# aepro_28C256.net
KiCad netlist of a schematic drawn in EAGLE
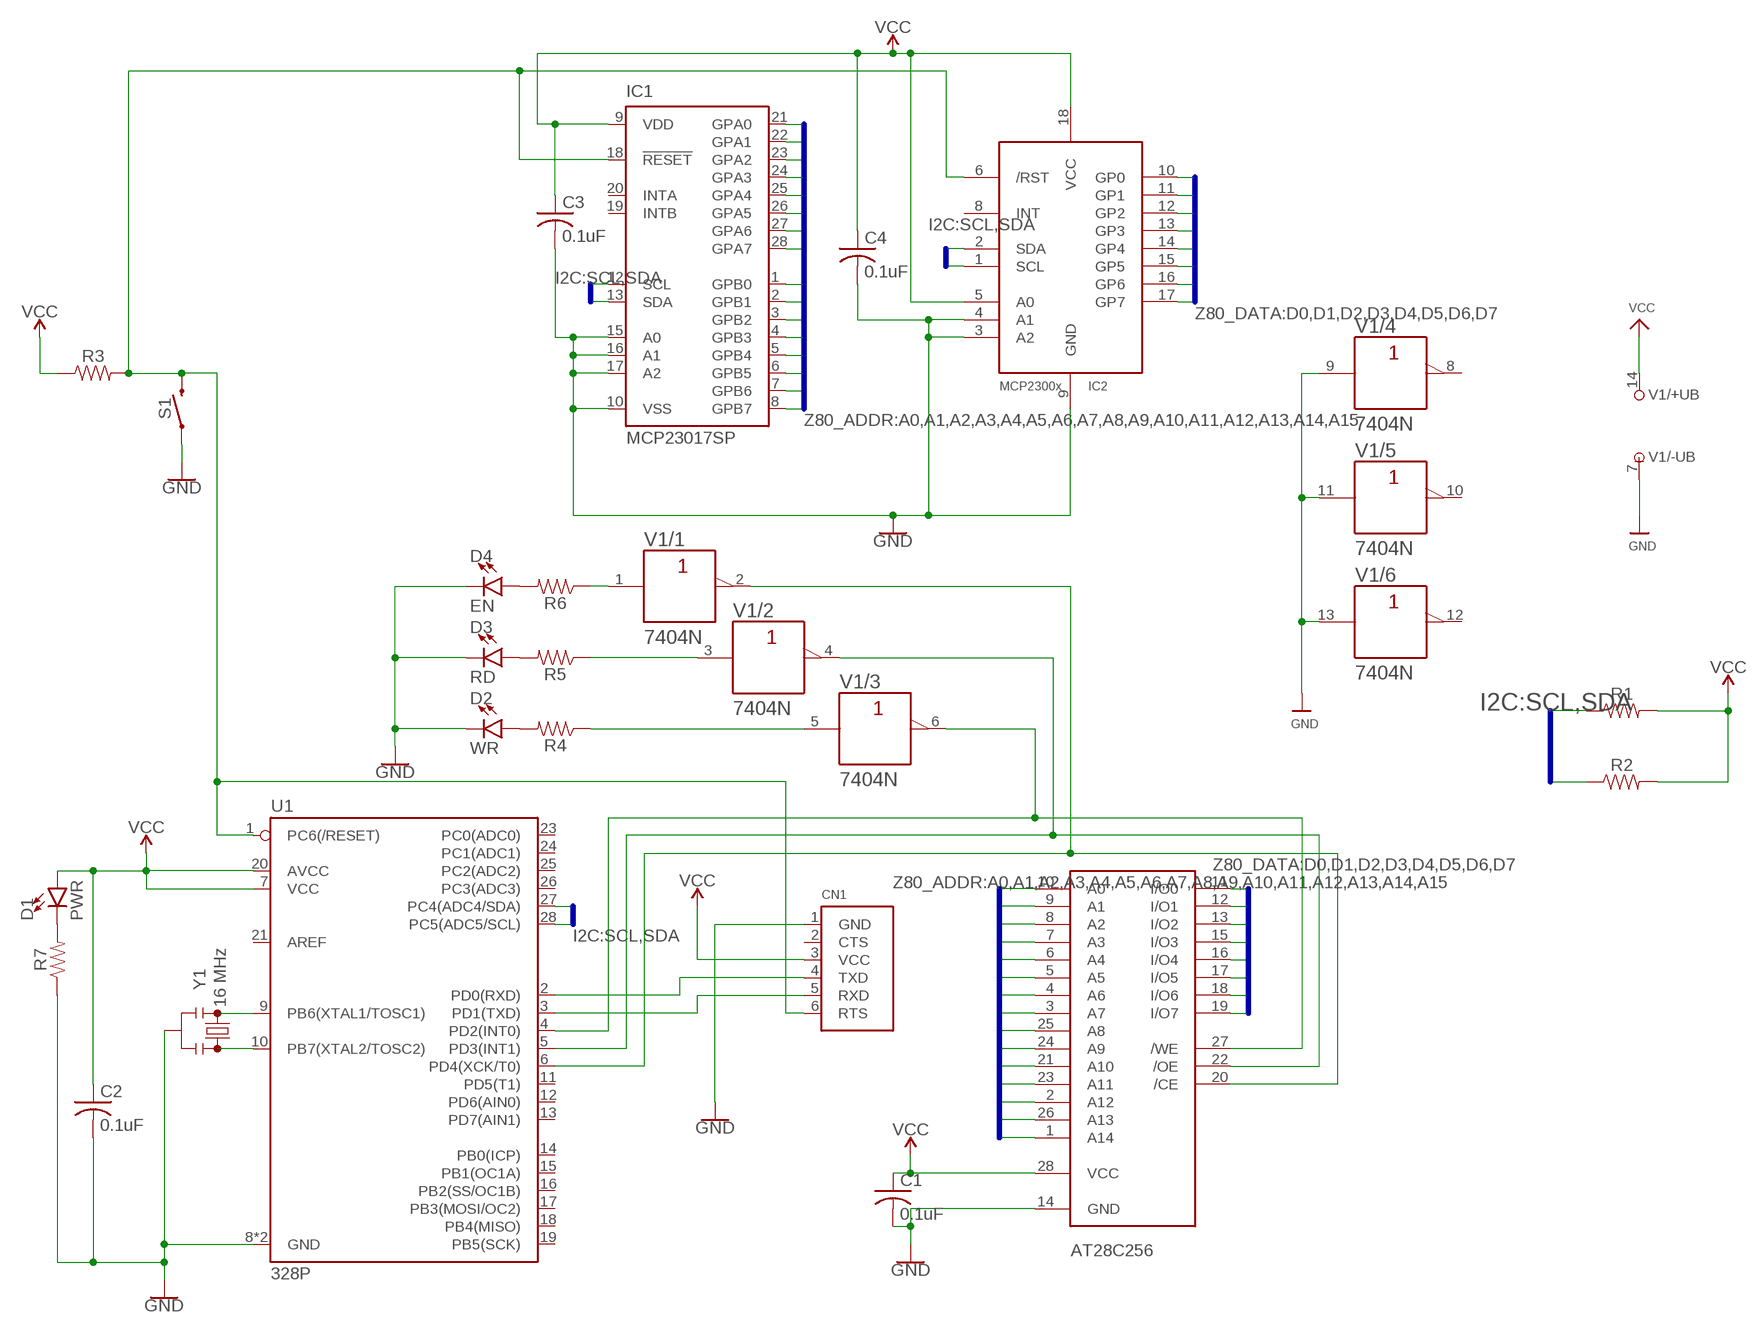
[diagram p0: schematic, sheet 1]

(export (version "E")
  (design (tool "Eeschema 10.0.6"))
  (components
    (comp (ref "C1")
      (value "0.1uF")
      (footprint "eagle-import:C050-024X044")
      (libsource (lib "eagle-import") (part "C-US050-024X044"))
    )
    (comp (ref "C2")
      (value "0.1uF")
      (footprint "eagle-import:C050-024X044")
      (libsource (lib "eagle-import") (part "C-US050-024X044"))
    )
    (comp (ref "C3")
      (value "0.1uF")
      (footprint "eagle-import:C050-024X044")
      (libsource (lib "eagle-import") (part "C-US050-024X044"))
    )
    (comp (ref "C4")
      (value "0.1uF")
      (footprint "eagle-import:C050-024X044")
      (libsource (lib "eagle-import") (part "C-US050-024X044"))
    )
    (comp (ref "CN1")
      (value "FTDIUSBCABLE")
      (footprint "eagle-import:1X06_ROUND")
      (libsource (lib "eagle-import") (part "FTDIUSBCABLE"))
    )
    (comp (ref "D1")
      (value "PWR")
      (footprint "eagle-import:LED_3MM")
      (libsource (lib "eagle-import") (part "LED3MM"))
    )
    (comp (ref "D2")
      (value "WR")
      (footprint "eagle-import:LED_3MM")
      (libsource (lib "eagle-import") (part "LED3MM"))
    )
    (comp (ref "D3")
      (value "RD")
      (footprint "eagle-import:LED_3MM")
      (libsource (lib "eagle-import") (part "LED3MM"))
    )
    (comp (ref "D4")
      (value "EN")
      (footprint "eagle-import:LED_3MM")
      (libsource (lib "eagle-import") (part "LED3MM"))
    )
    (comp (ref "IC1")
      (value "MCP23017SP")
      (footprint "eagle-import:DIL28-3")
      (libsource (lib "eagle-import") (part "MCP23017SP"))
    )
    (comp (ref "IC2")
      (value "MCP23008/P")
      (footprint "eagle-import:DIL18")
      (libsource (lib "eagle-import") (part "MCP23008/P"))
    )
    (comp (ref "R1")
      (value "RESISTORAXIAL-0.3")
      (footprint "eagle-import:AXIAL-0.3")
      (libsource (lib "eagle-import") (part "RESISTORAXIAL-0.3"))
    )
    (comp (ref "R2")
      (value "RESISTORAXIAL-0.3")
      (footprint "eagle-import:AXIAL-0.3")
      (libsource (lib "eagle-import") (part "RESISTORAXIAL-0.3"))
    )
    (comp (ref "R3")
      (value "RESISTORAXIAL-0.3")
      (footprint "eagle-import:AXIAL-0.3")
      (libsource (lib "eagle-import") (part "RESISTORAXIAL-0.3"))
    )
    (comp (ref "R4")
      (value "RESISTORAXIAL-0.3")
      (footprint "eagle-import:AXIAL-0.3")
      (libsource (lib "eagle-import") (part "RESISTORAXIAL-0.3"))
    )
    (comp (ref "R5")
      (value "RESISTORAXIAL-0.3")
      (footprint "eagle-import:AXIAL-0.3")
      (libsource (lib "eagle-import") (part "RESISTORAXIAL-0.3"))
    )
    (comp (ref "R6")
      (value "RESISTORAXIAL-0.3")
      (footprint "eagle-import:AXIAL-0.3")
      (libsource (lib "eagle-import") (part "RESISTORAXIAL-0.3"))
    )
    (comp (ref "R7")
      (value "RESISTORAXIAL-0.3")
      (footprint "eagle-import:AXIAL-0.3")
      (libsource (lib "eagle-import") (part "RESISTORAXIAL-0.3"))
    )
    (comp (ref "S1")
      (value "MOMENTARY-SWITCH-SPST-PTH-6.0MM")
      (footprint "eagle-import:TACTILE_SWITCH_PTH_6.0MM")
      (libsource (lib "eagle-import") (part "MOMENTARY-SWITCH-SPST-PTH-6.0MM"))
    )
    (comp (ref "U$1")
      (value "AT28C256")
      (footprint "eagle-import:DIL28-6-ZIF_SOCKET")
      (libsource (lib "eagle-import") (part "AT28C256"))
    )
    (comp (ref "U1")
      (value "328P")
      (footprint "eagle-import:DIP28")
      (libsource (lib "eagle-import") (part "ATMEGA328P_PDIP"))
    )
    (comp (ref "V1")
      (value "7404N")
      (footprint "eagle-import:DIL14")
      (libsource (lib "eagle-import") (part "7404N"))
    )
    (comp (ref "Y1")
      (value "16 MHz")
      (footprint "eagle-import:RESONATOR-PTH-7.6X3.8")
      (libsource (lib "eagle-import") (part "RESONATORPTH-7.6X3.8"))
    )
  )
  (nets
    (net (code "5") (name "/A1") (class "Default")
      (node (ref "IC1") (pin "22") (pinfunction "GPA1_22") (pintype "bidirectional"))
      (node (ref "U$1") (pin "9") (pinfunction "A1_9") (pintype "bidirectional"))
    )
    (net (code "6") (name "/A2") (class "Default")
      (node (ref "IC1") (pin "23") (pinfunction "GPA2_23") (pintype "bidirectional"))
      (node (ref "U$1") (pin "8") (pinfunction "A2_8") (pintype "bidirectional"))
    )
    (net (code "7") (name "/A3") (class "Default")
      (node (ref "IC1") (pin "24") (pinfunction "GPA3_24") (pintype "bidirectional"))
      (node (ref "U$1") (pin "7") (pinfunction "A3_7") (pintype "bidirectional"))
    )
    (net (code "8") (name "/A4") (class "Default")
      (node (ref "IC1") (pin "25") (pinfunction "GPA4_25") (pintype "bidirectional"))
      (node (ref "U$1") (pin "6") (pinfunction "A4_6") (pintype "bidirectional"))
    )
    (net (code "9") (name "/A5") (class "Default")
      (node (ref "IC1") (pin "26") (pinfunction "GPA5_26") (pintype "bidirectional"))
      (node (ref "U$1") (pin "5") (pinfunction "A5_5") (pintype "bidirectional"))
    )
    (net (code "10") (name "/A6") (class "Default")
      (node (ref "IC1") (pin "27") (pinfunction "GPA6_27") (pintype "bidirectional"))
      (node (ref "U$1") (pin "4") (pinfunction "A6_4") (pintype "bidirectional"))
    )
    (net (code "11") (name "/A7") (class "Default")
      (node (ref "IC1") (pin "28") (pinfunction "GPA7_28") (pintype "bidirectional"))
      (node (ref "U$1") (pin "3") (pinfunction "A7_3") (pintype "bidirectional"))
    )
    (net (code "12") (name "/A8") (class "Default")
      (node (ref "IC1") (pin "1") (pinfunction "GPB0_1") (pintype "bidirectional"))
      (node (ref "U$1") (pin "25") (pinfunction "A8_25") (pintype "bidirectional"))
    )
    (net (code "13") (name "/A9") (class "Default")
      (node (ref "IC1") (pin "2") (pinfunction "GPB1_2") (pintype "bidirectional"))
      (node (ref "U$1") (pin "24") (pinfunction "A9_24") (pintype "bidirectional"))
    )
    (net (code "14") (name "/A10") (class "Default")
      (node (ref "IC1") (pin "3") (pinfunction "GPB2_3") (pintype "bidirectional"))
      (node (ref "U$1") (pin "21") (pinfunction "A10_21") (pintype "bidirectional"))
    )
    (net (code "15") (name "/A11") (class "Default")
      (node (ref "IC1") (pin "4") (pinfunction "GPB3_4") (pintype "bidirectional"))
      (node (ref "U$1") (pin "23") (pinfunction "A11_23") (pintype "bidirectional"))
    )
    (net (code "16") (name "/A12") (class "Default")
      (node (ref "IC1") (pin "5") (pinfunction "GPB4_5") (pintype "bidirectional"))
      (node (ref "U$1") (pin "2") (pinfunction "A12_2") (pintype "bidirectional"))
    )
    (net (code "17") (name "/A13") (class "Default")
      (node (ref "IC1") (pin "6") (pinfunction "GPB5_6") (pintype "bidirectional"))
      (node (ref "U$1") (pin "26") (pinfunction "A13_26") (pintype "bidirectional"))
    )
    (net (code "18") (name "/A14") (class "Default")
      (node (ref "IC1") (pin "7") (pinfunction "GPB6_7") (pintype "bidirectional"))
      (node (ref "U$1") (pin "1") (pinfunction "A14_1") (pintype "bidirectional"))
    )
    (net (code "19") (name "/D1") (class "Default")
      (node (ref "IC2") (pin "11") (pinfunction "GP1_11") (pintype "bidirectional"))
      (node (ref "U$1") (pin "12") (pinfunction "I/O1_12") (pintype "bidirectional"))
    )
    (net (code "20") (name "/D2") (class "Default")
      (node (ref "IC2") (pin "12") (pinfunction "GP2_12") (pintype "bidirectional"))
      (node (ref "U$1") (pin "13") (pinfunction "I/O2_13") (pintype "bidirectional"))
    )
    (net (code "21") (name "/D3") (class "Default")
      (node (ref "IC2") (pin "13") (pinfunction "GP3_13") (pintype "bidirectional"))
      (node (ref "U$1") (pin "15") (pinfunction "I/O3_15") (pintype "bidirectional"))
    )
    (net (code "22") (name "/D4") (class "Default")
      (node (ref "IC2") (pin "14") (pinfunction "GP4_14") (pintype "bidirectional"))
      (node (ref "U$1") (pin "16") (pinfunction "I/O4_16") (pintype "bidirectional"))
    )
    (net (code "23") (name "/D5") (class "Default")
      (node (ref "IC2") (pin "15") (pinfunction "GP5_15") (pintype "bidirectional"))
      (node (ref "U$1") (pin "17") (pinfunction "I/O5_17") (pintype "bidirectional"))
    )
    (net (code "24") (name "/D6") (class "Default")
      (node (ref "IC2") (pin "16") (pinfunction "GP6_16") (pintype "bidirectional"))
      (node (ref "U$1") (pin "18") (pinfunction "I/O6_18") (pintype "bidirectional"))
    )
    (net (code "25") (name "/D7") (class "Default")
      (node (ref "IC2") (pin "17") (pinfunction "GP7_17") (pintype "bidirectional"))
      (node (ref "U$1") (pin "19") (pinfunction "I/O7_19") (pintype "bidirectional"))
    )
    (net (code "26") (name "/I2C:SCL") (class "Default")
      (node (ref "IC1") (pin "12") (pinfunction "SCL_12") (pintype "input"))
      (node (ref "IC2") (pin "1") (pinfunction "SCL_1") (pintype "bidirectional"))
      (node (ref "R1") (pin "P$1") (pinfunction "1_P$1") (pintype "passive"))
      (node (ref "U1") (pin "28") (pinfunction "PC5(ADC5/SCL)_28") (pintype "bidirectional"))
    )
    (net (code "27") (name "/SDA") (class "Default")
      (node (ref "IC1") (pin "13") (pinfunction "SDA_13") (pintype "bidirectional"))
      (node (ref "IC2") (pin "2") (pinfunction "SDA_2") (pintype "bidirectional"))
      (node (ref "R2") (pin "P$1") (pinfunction "1_P$1") (pintype "passive"))
      (node (ref "U1") (pin "27") (pinfunction "PC4(ADC4/SDA)_27") (pintype "bidirectional"))
    )
    (net (code "28") (name "/Z80_ADDR:A0") (class "Default")
      (node (ref "IC1") (pin "21") (pinfunction "GPA0_21") (pintype "bidirectional"))
      (node (ref "U$1") (pin "10") (pinfunction "A0_10") (pintype "bidirectional"))
    )
    (net (code "29") (name "/Z80_DATA:D0") (class "Default")
      (node (ref "IC2") (pin "10") (pinfunction "GP0_10") (pintype "bidirectional"))
      (node (ref "U$1") (pin "11") (pinfunction "I/O0_11") (pintype "bidirectional"))
    )
    (net (code "33") (name "GND") (class "Default")
      (node (ref "C1") (pin "2") (pinfunction "2_2") (pintype "passive"))
      (node (ref "C2") (pin "2") (pinfunction "2_2") (pintype "passive"))
      (node (ref "C3") (pin "2") (pinfunction "2_2") (pintype "passive"))
      (node (ref "C4") (pin "2") (pinfunction "2_2") (pintype "passive"))
      (node (ref "CN1") (pin "1") (pinfunction "GND_1") (pintype "bidirectional"))
      (node (ref "D2") (pin "K") (pinfunction "C_K") (pintype "passive"))
      (node (ref "D3") (pin "K") (pinfunction "C_K") (pintype "passive"))
      (node (ref "D4") (pin "K") (pinfunction "C_K") (pintype "passive"))
      (node (ref "IC1") (pin "10") (pinfunction "VSS_10") (pintype "power_in"))
      (node (ref "IC1") (pin "15") (pinfunction "A0_15") (pintype "input"))
      (node (ref "IC1") (pin "16") (pinfunction "A1_16") (pintype "input"))
      (node (ref "IC1") (pin "17") (pinfunction "A2_17") (pintype "input"))
      (node (ref "IC2") (pin "3") (pinfunction "A2_3") (pintype "input"))
      (node (ref "IC2") (pin "4") (pinfunction "A1_4") (pintype "input"))
      (node (ref "IC2") (pin "9") (pinfunction "GND_9") (pintype "power_in"))
      (node (ref "R7") (pin "P$1") (pinfunction "1_P$1") (pintype "passive"))
      (node (ref "S1") (pin "1") (pinfunction "1_1") (pintype "passive"))
      (node (ref "U$1") (pin "14") (pinfunction "GND_14") (pintype "bidirectional"))
      (node (ref "U1") (pin "22") (pinfunction "GND_22") (pintype "bidirectional"))
      (node (ref "U1") (pin "8") (pinfunction "GND_8") (pintype "bidirectional"))
      (node (ref "V1") (pin "11") (pinfunction "A_11") (pintype "input"))
      (node (ref "V1") (pin "13") (pinfunction "A_13") (pintype "input"))
      (node (ref "V1") (pin "7") (pinfunction "-UB_7") (pintype "power_in"))
      (node (ref "V1") (pin "9") (pinfunction "A_9") (pintype "input"))
      (node (ref "Y1") (pin "2") (pinfunction "2_2") (pintype "passive"))
    )
    (net (code "34") (name "Net-(CN1-RTS)") (class "Default")
      (node (ref "CN1") (pin "6") (pinfunction "RTS_6") (pintype "bidirectional"))
      (node (ref "IC1") (pin "18") (pinfunction "~{RESET}_18") (pintype "input"))
      (node (ref "IC2") (pin "6") (pinfunction "/RST_6") (pintype "input"))
      (node (ref "R3") (pin "P$2") (pinfunction "2_P$2") (pintype "passive"))
      (node (ref "S1") (pin "3") (pinfunction "2_3") (pintype "passive"))
      (node (ref "U1") (pin "1") (pinfunction "PC6(/RESET)_1") (pintype "bidirectional"))
    )
    (net (code "35") (name "Net-(CN1-RXD)") (class "Default")
      (node (ref "CN1") (pin "5") (pinfunction "RXD_5") (pintype "bidirectional"))
      (node (ref "U1") (pin "3") (pinfunction "PD1(TXD)_3") (pintype "bidirectional"))
    )
    (net (code "36") (name "Net-(CN1-TXD)") (class "Default")
      (node (ref "CN1") (pin "4") (pinfunction "TXD_4") (pintype "bidirectional"))
      (node (ref "U1") (pin "2") (pinfunction "PD0(RXD)_2") (pintype "bidirectional"))
    )
    (net (code "37") (name "Net-(D1-C)") (class "Default")
      (node (ref "D1") (pin "K") (pinfunction "C_K") (pintype "passive"))
      (node (ref "R7") (pin "P$2") (pinfunction "2_P$2") (pintype "passive"))
    )
    (net (code "38") (name "Net-(R4-1)") (class "Default")
      (node (ref "R4") (pin "P$1") (pinfunction "1_P$1") (pintype "passive"))
      (node (ref "V1") (pin "5") (pinfunction "A_5") (pintype "input"))
    )
    (net (code "39") (name "Net-(R4-2)") (class "Default")
      (node (ref "D2") (pin "A") (pinfunction "A_A") (pintype "passive"))
      (node (ref "R4") (pin "P$2") (pinfunction "2_P$2") (pintype "passive"))
    )
    (net (code "40") (name "Net-(R5-1)") (class "Default")
      (node (ref "R5") (pin "P$1") (pinfunction "1_P$1") (pintype "passive"))
      (node (ref "V1") (pin "3") (pinfunction "A_3") (pintype "input"))
    )
    (net (code "41") (name "Net-(R5-2)") (class "Default")
      (node (ref "D3") (pin "A") (pinfunction "A_A") (pintype "passive"))
      (node (ref "R5") (pin "P$2") (pinfunction "2_P$2") (pintype "passive"))
    )
    (net (code "42") (name "Net-(R6-1)") (class "Default")
      (node (ref "R6") (pin "P$1") (pinfunction "1_P$1") (pintype "passive"))
      (node (ref "V1") (pin "1") (pinfunction "A_1") (pintype "input"))
    )
    (net (code "43") (name "Net-(R6-2)") (class "Default")
      (node (ref "D4") (pin "A") (pinfunction "A_A") (pintype "passive"))
      (node (ref "R6") (pin "P$2") (pinfunction "2_P$2") (pintype "passive"))
    )
    (net (code "44") (name "Net-(U$1-{slash}CE)") (class "Default")
      (node (ref "U$1") (pin "20") (pinfunction "/CE_20") (pintype "bidirectional"))
      (node (ref "U1") (pin "6") (pinfunction "PD4(XCK/T0)_6") (pintype "bidirectional"))
      (node (ref "V1") (pin "2") (pinfunction "Y_2") (pintype "output"))
    )
    (net (code "45") (name "Net-(U$1-{slash}OE)") (class "Default")
      (node (ref "U$1") (pin "22") (pinfunction "/OE_22") (pintype "bidirectional"))
      (node (ref "U1") (pin "5") (pinfunction "PD3(INT1)_5") (pintype "bidirectional"))
      (node (ref "V1") (pin "4") (pinfunction "Y_4") (pintype "output"))
    )
    (net (code "46") (name "Net-(U$1-{slash}WE)") (class "Default")
      (node (ref "U$1") (pin "27") (pinfunction "/WE_27") (pintype "bidirectional"))
      (node (ref "U1") (pin "4") (pinfunction "PD2(INT0)_4") (pintype "bidirectional"))
      (node (ref "V1") (pin "6") (pinfunction "Y_6") (pintype "output"))
    )
    (net (code "47") (name "Net-(U1-PB6(XTAL1{slash}TOSC1))") (class "Default")
      (node (ref "U1") (pin "9") (pinfunction "PB6(XTAL1/TOSC1)_9") (pintype "bidirectional"))
      (node (ref "Y1") (pin "1") (pinfunction "1_1") (pintype "passive"))
    )
    (net (code "48") (name "Net-(U1-PB7(XTAL2{slash}TOSC2))") (class "Default")
      (node (ref "U1") (pin "10") (pinfunction "PB7(XTAL2/TOSC2)_10") (pintype "bidirectional"))
      (node (ref "Y1") (pin "3") (pinfunction "3_3") (pintype "passive"))
    )
    (net (code "49") (name "VCC") (class "Default")
      (node (ref "C1") (pin "1") (pinfunction "1_1") (pintype "passive"))
      (node (ref "C2") (pin "1") (pinfunction "1_1") (pintype "passive"))
      (node (ref "C3") (pin "1") (pinfunction "1_1") (pintype "passive"))
      (node (ref "C4") (pin "1") (pinfunction "1_1") (pintype "passive"))
      (node (ref "CN1") (pin "3") (pinfunction "VCC_3") (pintype "bidirectional"))
      (node (ref "D1") (pin "A") (pinfunction "A_A") (pintype "passive"))
      (node (ref "IC1") (pin "9") (pinfunction "VDD_9") (pintype "power_in"))
      (node (ref "IC2") (pin "18") (pinfunction "VCC_18") (pintype "power_in"))
      (node (ref "IC2") (pin "5") (pinfunction "A0_5") (pintype "input"))
      (node (ref "R1") (pin "P$2") (pinfunction "2_P$2") (pintype "passive"))
      (node (ref "R2") (pin "P$2") (pinfunction "2_P$2") (pintype "passive"))
      (node (ref "R3") (pin "P$1") (pinfunction "1_P$1") (pintype "passive"))
      (node (ref "U$1") (pin "28") (pinfunction "VCC_28") (pintype "bidirectional"))
      (node (ref "U1") (pin "20") (pinfunction "AVCC_20") (pintype "bidirectional"))
      (node (ref "U1") (pin "7") (pinfunction "VCC_7") (pintype "bidirectional"))
      (node (ref "V1") (pin "14") (pinfunction "+UB_14") (pintype "power_in"))
    )
    (net (code "50") (name "unconnected-(CN1-CTS-Pad2)") (class "Default")
      (node (ref "CN1") (pin "2") (pinfunction "CTS_2") (pintype "bidirectional"))
    )
    (net (code "51") (name "unconnected-(IC1-GPB7-Pad8)") (class "Default")
      (node (ref "IC1") (pin "8") (pinfunction "GPB7_8") (pintype "bidirectional"))
    )
    (net (code "52") (name "unconnected-(IC1-INTA-Pad20)") (class "Default")
      (node (ref "IC1") (pin "20") (pinfunction "INTA_20") (pintype "output"))
    )
    (net (code "53") (name "unconnected-(IC1-INTB-Pad19)") (class "Default")
      (node (ref "IC1") (pin "19") (pinfunction "INTB_19") (pintype "output"))
    )
    (net (code "54") (name "unconnected-(IC2-INT-Pad8)") (class "Default")
      (node (ref "IC2") (pin "8") (pinfunction "INT_8") (pintype "output"))
    )
    (net (code "55") (name "unconnected-(U1-AREF-Pad21)") (class "Default")
      (node (ref "U1") (pin "21") (pinfunction "AREF_21") (pintype "bidirectional"))
    )
    (net (code "56") (name "unconnected-(U1-PB0(ICP)-Pad14)") (class "Default")
      (node (ref "U1") (pin "14") (pinfunction "PB0(ICP)_14") (pintype "bidirectional"))
    )
    (net (code "57") (name "unconnected-(U1-PB1(OC1A)-Pad15)") (class "Default")
      (node (ref "U1") (pin "15") (pinfunction "PB1(OC1A)_15") (pintype "bidirectional"))
    )
    (net (code "58") (name "unconnected-(U1-PB2(SS{slash}OC1B)-Pad16)") (class "Default")
      (node (ref "U1") (pin "16") (pinfunction "PB2(SS/OC1B)_16") (pintype "bidirectional"))
    )
    (net (code "59") (name "unconnected-(U1-PB3(MOSI{slash}OC2)-Pad17)") (class "Default")
      (node (ref "U1") (pin "17") (pinfunction "PB3(MOSI/OC2)_17") (pintype "bidirectional"))
    )
    (net (code "60") (name "unconnected-(U1-PB4(MISO)-Pad18)") (class "Default")
      (node (ref "U1") (pin "18") (pinfunction "PB4(MISO)_18") (pintype "bidirectional"))
    )
    (net (code "61") (name "unconnected-(U1-PB5(SCK)-Pad19)") (class "Default")
      (node (ref "U1") (pin "19") (pinfunction "PB5(SCK)_19") (pintype "bidirectional"))
    )
    (net (code "62") (name "unconnected-(U1-PC0(ADC0)-Pad23)") (class "Default")
      (node (ref "U1") (pin "23") (pinfunction "PC0(ADC0)_23") (pintype "bidirectional"))
    )
    (net (code "63") (name "unconnected-(U1-PC1(ADC1)-Pad24)") (class "Default")
      (node (ref "U1") (pin "24") (pinfunction "PC1(ADC1)_24") (pintype "bidirectional"))
    )
    (net (code "64") (name "unconnected-(U1-PC2(ADC2)-Pad25)") (class "Default")
      (node (ref "U1") (pin "25") (pinfunction "PC2(ADC2)_25") (pintype "bidirectional"))
    )
    (net (code "65") (name "unconnected-(U1-PC3(ADC3)-Pad26)") (class "Default")
      (node (ref "U1") (pin "26") (pinfunction "PC3(ADC3)_26") (pintype "bidirectional"))
    )
    (net (code "66") (name "unconnected-(U1-PD5(T1)-Pad11)") (class "Default")
      (node (ref "U1") (pin "11") (pinfunction "PD5(T1)_11") (pintype "bidirectional"))
    )
    (net (code "67") (name "unconnected-(U1-PD6(AIN0)-Pad12)") (class "Default")
      (node (ref "U1") (pin "12") (pinfunction "PD6(AIN0)_12") (pintype "bidirectional"))
    )
    (net (code "68") (name "unconnected-(U1-PD7(AIN1)-Pad13)") (class "Default")
      (node (ref "U1") (pin "13") (pinfunction "PD7(AIN1)_13") (pintype "bidirectional"))
    )
    (net (code "69") (name "unconnected-(V1F-Y-Pad8)") (class "Default")
      (node (ref "V1") (pin "8") (pinfunction "Y_8") (pintype "output"))
    )
    (net (code "70") (name "unconnected-(V1G-Y-Pad10)") (class "Default")
      (node (ref "V1") (pin "10") (pinfunction "Y_10") (pintype "output"))
    )
    (net (code "71") (name "unconnected-(V1H-Y-Pad12)") (class "Default")
      (node (ref "V1") (pin "12") (pinfunction "Y_12") (pintype "output"))
    )
  )
)
